# En_V1.net
KiCad netlist of a schematic drawn in Altium Designer
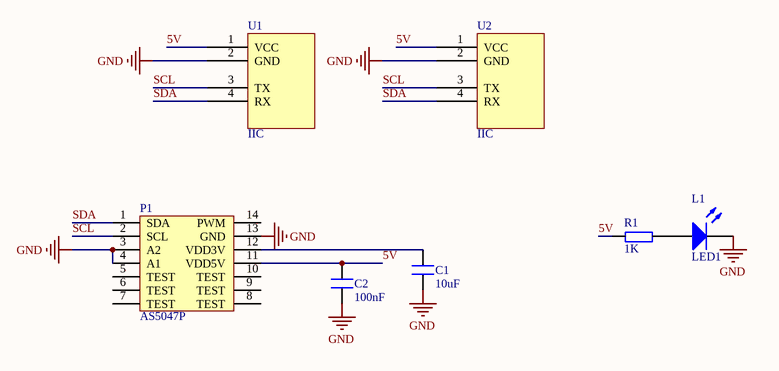
[diagram p0: En_V1.SchDoc]

(export (version "E")
  (design (tool "Eeschema 10.0.6"))
  (components
    (comp (ref "C1") (value "10uF") (footprint "0603P") (libsource (lib "Explorer STM32F407封装库") (part "C")))
    (comp (ref "C2") (value "100nF") (footprint "0603P") (libsource (lib "Explorer STM32F407封装库") (part "C")))
    (comp (ref "L1")
      (value "LED1")
      (footprint "0603_LED")
      (description "Typical RED, GREEN, YELLOW, AMBER GaAs LED")
      (fields (field (name "PUBLISHER") "Altium Limited"))
      (libsource (lib "Explorer STM32F407封装库") (part "LED2"))
    )
    (comp (ref "P1")
      (value "AS5047P")
      (footprint "TSSOP-14")
      (libsource (lib "SCHlib") (part "AS5048B-TSSOP14_1"))
    )
    (comp (ref "R1") (value "1K") (footprint "0603P") (libsource (lib "Explorer STM32F407封装库") (part "R")))
    (comp (ref "U1") (value "IIC") (footprint "XH2.54-4") (libsource (lib "羽毛球团队") (part "XH2.54插座-4P")))
    (comp (ref "U2") (value "IIC") (footprint "XH2.54-4") (libsource (lib "羽毛球团队") (part "XH2.54插座-4P")))
  )
  (nets
    (net (code "1") (name "/5V") (class "Default")
      (node (ref "C2") (pin "2") (pintype "passive"))
      (node (ref "P1") (pin "11") (pinfunction "VDD5V_11") (pintype "passive"))
      (node (ref "R1") (pin "1") (pintype "passive"))
      (node (ref "U1") (pin "1") (pinfunction "VCC_1") (pintype "passive"))
      (node (ref "U2") (pin "1") (pinfunction "VCC_1") (pintype "passive"))
    )
    (net (code "2") (name "/SCL") (class "Default")
      (node (ref "P1") (pin "2") (pinfunction "SCL_2") (pintype "passive"))
      (node (ref "U1") (pin "3") (pinfunction "TX_3") (pintype "passive"))
      (node (ref "U2") (pin "3") (pinfunction "TX_3") (pintype "passive"))
    )
    (net (code "3") (name "/SDA") (class "Default")
      (node (ref "P1") (pin "1") (pinfunction "SDA_1") (pintype "passive"))
      (node (ref "U1") (pin "4") (pinfunction "RX_4") (pintype "passive"))
      (node (ref "U2") (pin "4") (pinfunction "RX_4") (pintype "passive"))
    )
    (net (code "4") (name "GND") (class "Default")
      (node (ref "C1") (pin "1") (pintype "passive"))
      (node (ref "C2") (pin "1") (pintype "passive"))
      (node (ref "L1") (pin "2") (pinfunction "K_2") (pintype "passive"))
      (node (ref "P1") (pin "13") (pinfunction "GND_13") (pintype "passive"))
      (node (ref "P1") (pin "3") (pinfunction "A2_3") (pintype "passive"))
      (node (ref "P1") (pin "4") (pinfunction "A1_4") (pintype "passive"))
      (node (ref "U1") (pin "2") (pinfunction "GND_2") (pintype "passive"))
      (node (ref "U2") (pin "2") (pinfunction "GND_2") (pintype "passive"))
    )
    (net (code "5") (name "Net-(L1-A)") (class "Default")
      (node (ref "L1") (pin "1") (pinfunction "A_1") (pintype "passive"))
      (node (ref "R1") (pin "2") (pintype "passive"))
    )
    (net (code "6") (name "Net-(P1-VDD3V)") (class "Default")
      (node (ref "C1") (pin "2") (pintype "passive"))
      (node (ref "P1") (pin "12") (pinfunction "VDD3V_12") (pintype "passive"))
    )
    (net (code "7") (name "unconnected-(P1-PWM-Pad14)") (class "Default")
      (node (ref "P1") (pin "14") (pinfunction "PWM_14") (pintype "passive"))
    )
    (net (code "8") (name "unconnected-(P1-TEST-Pad5)") (class "Default")
      (node (ref "P1") (pin "5") (pinfunction "TEST_5") (pintype "passive"))
    )
    (net (code "9") (name "unconnected-(P1-TEST-Pad6)") (class "Default")
      (node (ref "P1") (pin "6") (pinfunction "TEST_6") (pintype "passive"))
    )
    (net (code "10") (name "unconnected-(P1-TEST-Pad7)") (class "Default")
      (node (ref "P1") (pin "7") (pinfunction "TEST_7") (pintype "passive"))
    )
    (net (code "11") (name "unconnected-(P1-TEST-Pad8)") (class "Default")
      (node (ref "P1") (pin "8") (pinfunction "TEST_8") (pintype "passive"))
    )
    (net (code "12") (name "unconnected-(P1-TEST-Pad9)") (class "Default")
      (node (ref "P1") (pin "9") (pinfunction "TEST_9") (pintype "passive"))
    )
    (net (code "13") (name "unconnected-(P1-TEST-Pad10)") (class "Default")
      (node (ref "P1") (pin "10") (pinfunction "TEST_10") (pintype "passive"))
    )
  )
)
